# Teslamodell_1.net
KiCad netlist of a schematic drawn in Altium Designer
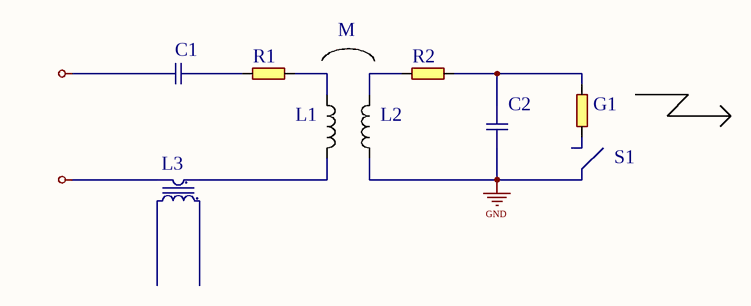
[diagram p0: Teslamodell_1.SchDoc]

(export (version "E")
  (design (tool "Eeschema 10.0.6"))
  (components
    (comp (ref "C1")
      (value "PC/HV/S/WF 22NF")
      (footprint "CAPAD340W1L280D11B")
      (description "CAP, FILM, PP, 22NF, 1.5KV, AXIAL")
      (libsource (lib "OVLib") (part "CAP"))
    )
    (comp (ref "C2")
      (value "PC/HV/S/WF 22NF")
      (footprint "CAPAD340W1L280D11B")
      (description "CAP, FILM, PP, 22NF, 1.5KV, AXIAL")
      (libsource (lib "OVLib") (part "CAP"))
    )
    (comp (ref "G1")
      (value "10")
      (footprint "RESA_0.25W")
      (description "0.25W 1% Generic resistor")
      (libsource (lib "") (part "Resistor2_2"))
    )
    (comp (ref "L1")
      (value "SMD spoler")
      (footprint "INDP3225X20N")
      (description "SMD inductors og tomme SMD bokser")
      (libsource (lib "OVLib") (part "IND_GENERIC"))
    )
    (comp (ref "L2")
      (value "SMD spoler")
      (footprint "INDP3225X20N")
      (description "SMD inductors og tomme SMD bokser")
      (libsource (lib "OVLib") (part "IND_GENERIC"))
    )
    (comp (ref "L3")
      (value "CurrentSenseTransformer")
      (libsource (lib "OVLib") (part "Current_sensing_transformer"))
    )
    (comp (ref "R1")
      (value "10")
      (footprint "RESA_0.25W")
      (description "0.25W 1% Generic resistor")
      (libsource (lib "") (part "Resistor2_1"))
    )
    (comp (ref "R2")
      (value "10")
      (footprint "RESA_0.25W")
      (description "0.25W 1% Generic resistor")
      (libsource (lib "OVLib") (part "Resistor2"))
    )
  )
  (nets
    (net (code "1") (name "GND") (class "Default")
      (node (ref "C2") (pin "1") (pinfunction "1_1") (pintype "passive"))
      (node (ref "L2") (pin "1") (pinfunction "1_1") (pintype "passive"))
    )
    (net (code "2") (name "Net-(C1-Pad2)") (class "Default")
      (node (ref "C1") (pin "2") (pinfunction "2_2") (pintype "passive"))
      (node (ref "R1") (pin "1") (pinfunction "1_1") (pintype "passive"))
    )
    (net (code "3") (name "Net-(C2-Pad2)") (class "Default")
      (node (ref "C2") (pin "2") (pinfunction "2_2") (pintype "passive"))
      (node (ref "G1") (pin "2") (pinfunction "2_2") (pintype "passive"))
      (node (ref "R2") (pin "1") (pinfunction "1_1") (pintype "passive"))
    )
    (net (code "4") (name "Net-(L1-Pad1)") (class "Default")
      (node (ref "L1") (pin "1") (pinfunction "1_1") (pintype "passive"))
      (node (ref "R1") (pin "2") (pinfunction "2_2") (pintype "passive"))
    )
    (net (code "5") (name "Net-(L1-Pad2)") (class "Default")
      (node (ref "L1") (pin "2") (pinfunction "2_2") (pintype "passive"))
      (node (ref "L3") (pin "2") (pinfunction "2_2") (pintype "passive"))
    )
    (net (code "6") (name "Net-(L2-Pad2)") (class "Default")
      (node (ref "L2") (pin "2") (pinfunction "2_2") (pintype "passive"))
      (node (ref "R2") (pin "2") (pinfunction "2_2") (pintype "passive"))
    )
    (net (code "7") (name "VCC") (class "Default")
      (node (ref "C1") (pin "1") (pinfunction "1_1") (pintype "passive"))
      (node (ref "L3") (pin "1") (pinfunction "1_1") (pintype "passive"))
    )
    (net (code "8") (name "unconnected-(G1-Pad1)") (class "Default")
      (node (ref "G1") (pin "1") (pinfunction "1_1") (pintype "passive"))
    )
    (net (code "9") (name "unconnected-(L3-Pad3)") (class "Default")
      (node (ref "L3") (pin "3") (pinfunction "3_3") (pintype "passive"))
    )
    (net (code "10") (name "unconnected-(L3-Pad4)") (class "Default")
      (node (ref "L3") (pin "4") (pinfunction "4_4") (pintype "passive"))
    )
  )
)
